# ADDINBRD2_V1.net
KiCad netlist of a schematic drawn in EAGLE
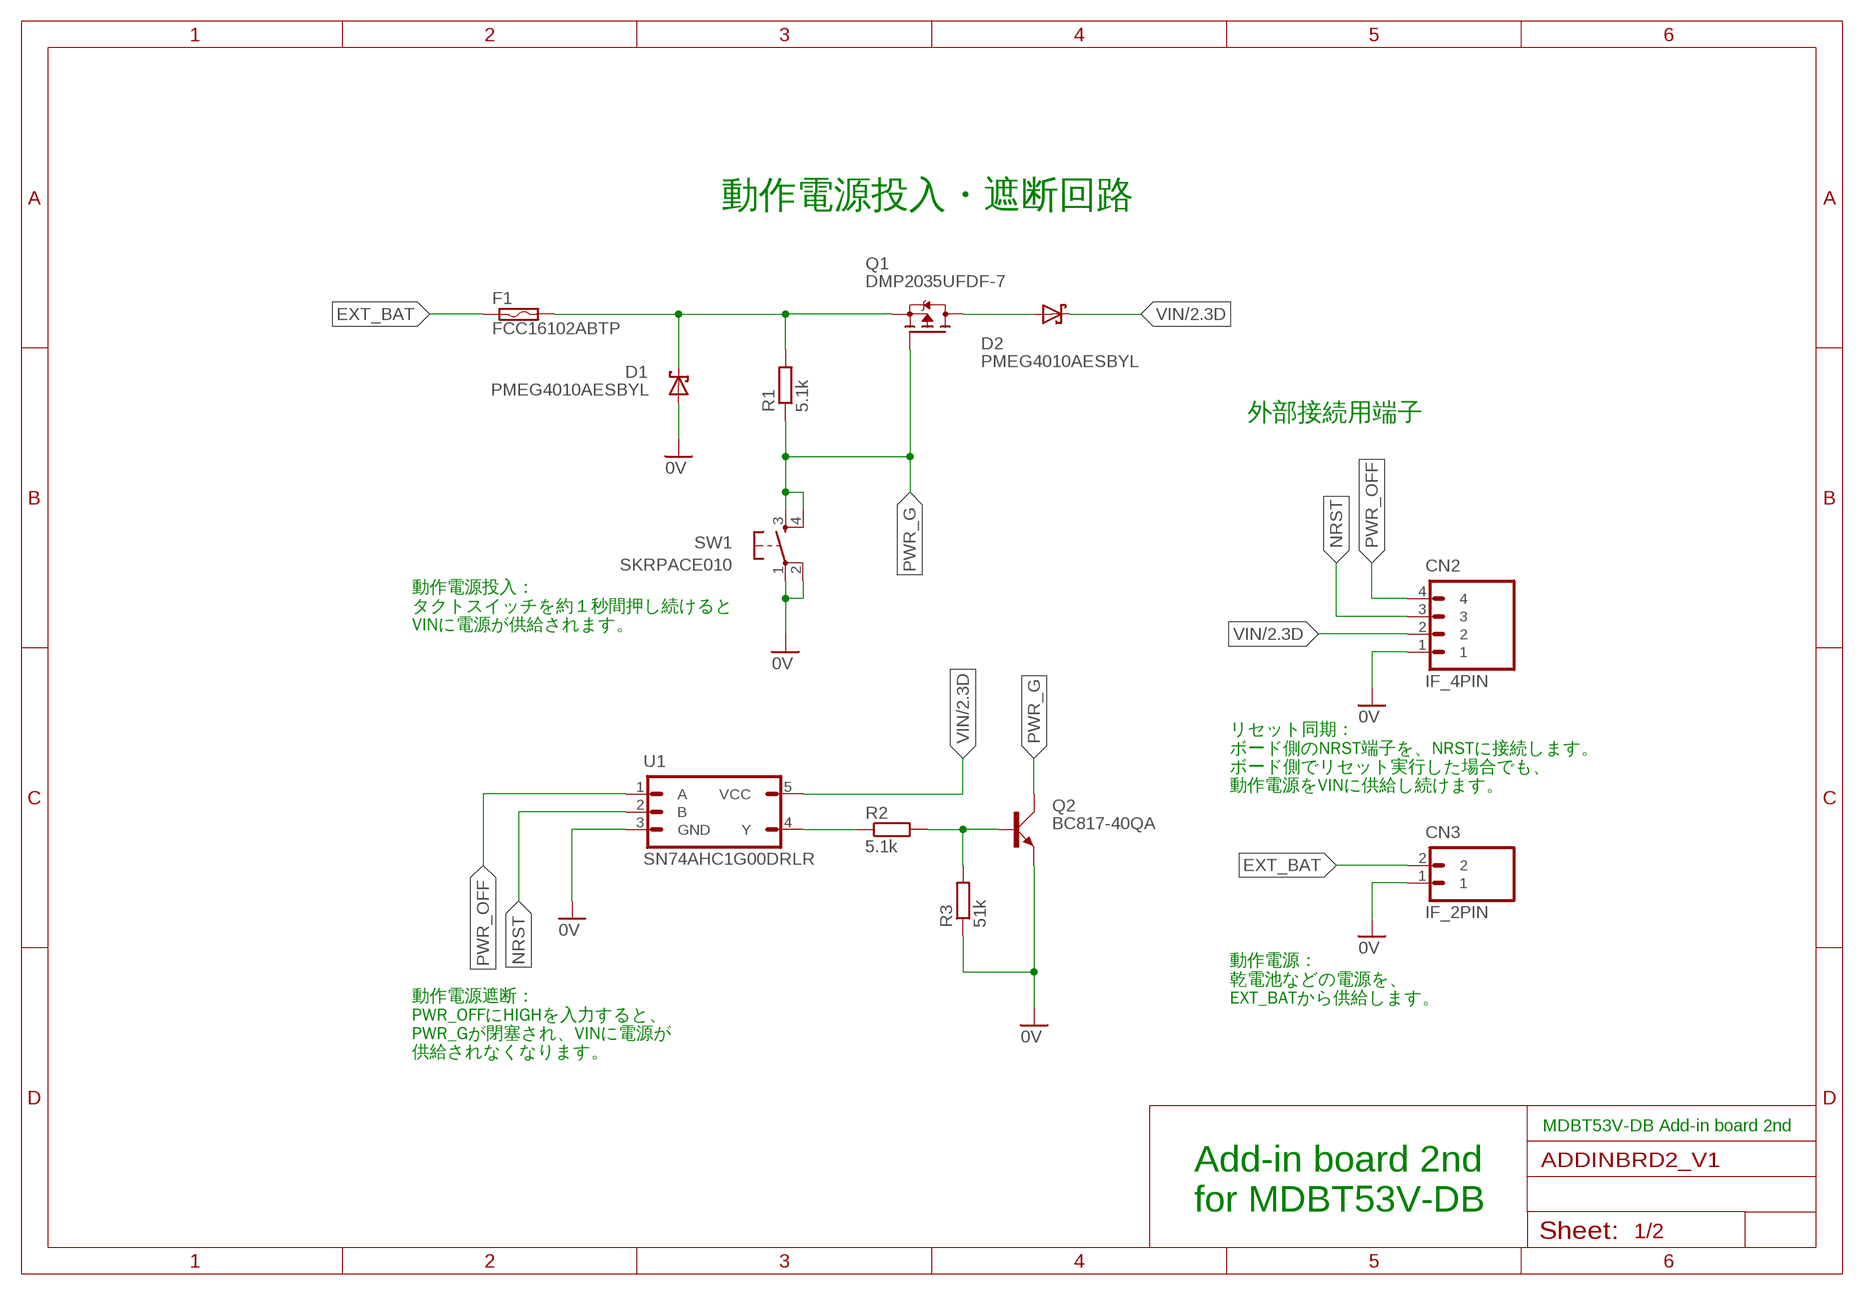
[diagram p0: schematic, sheet 1]
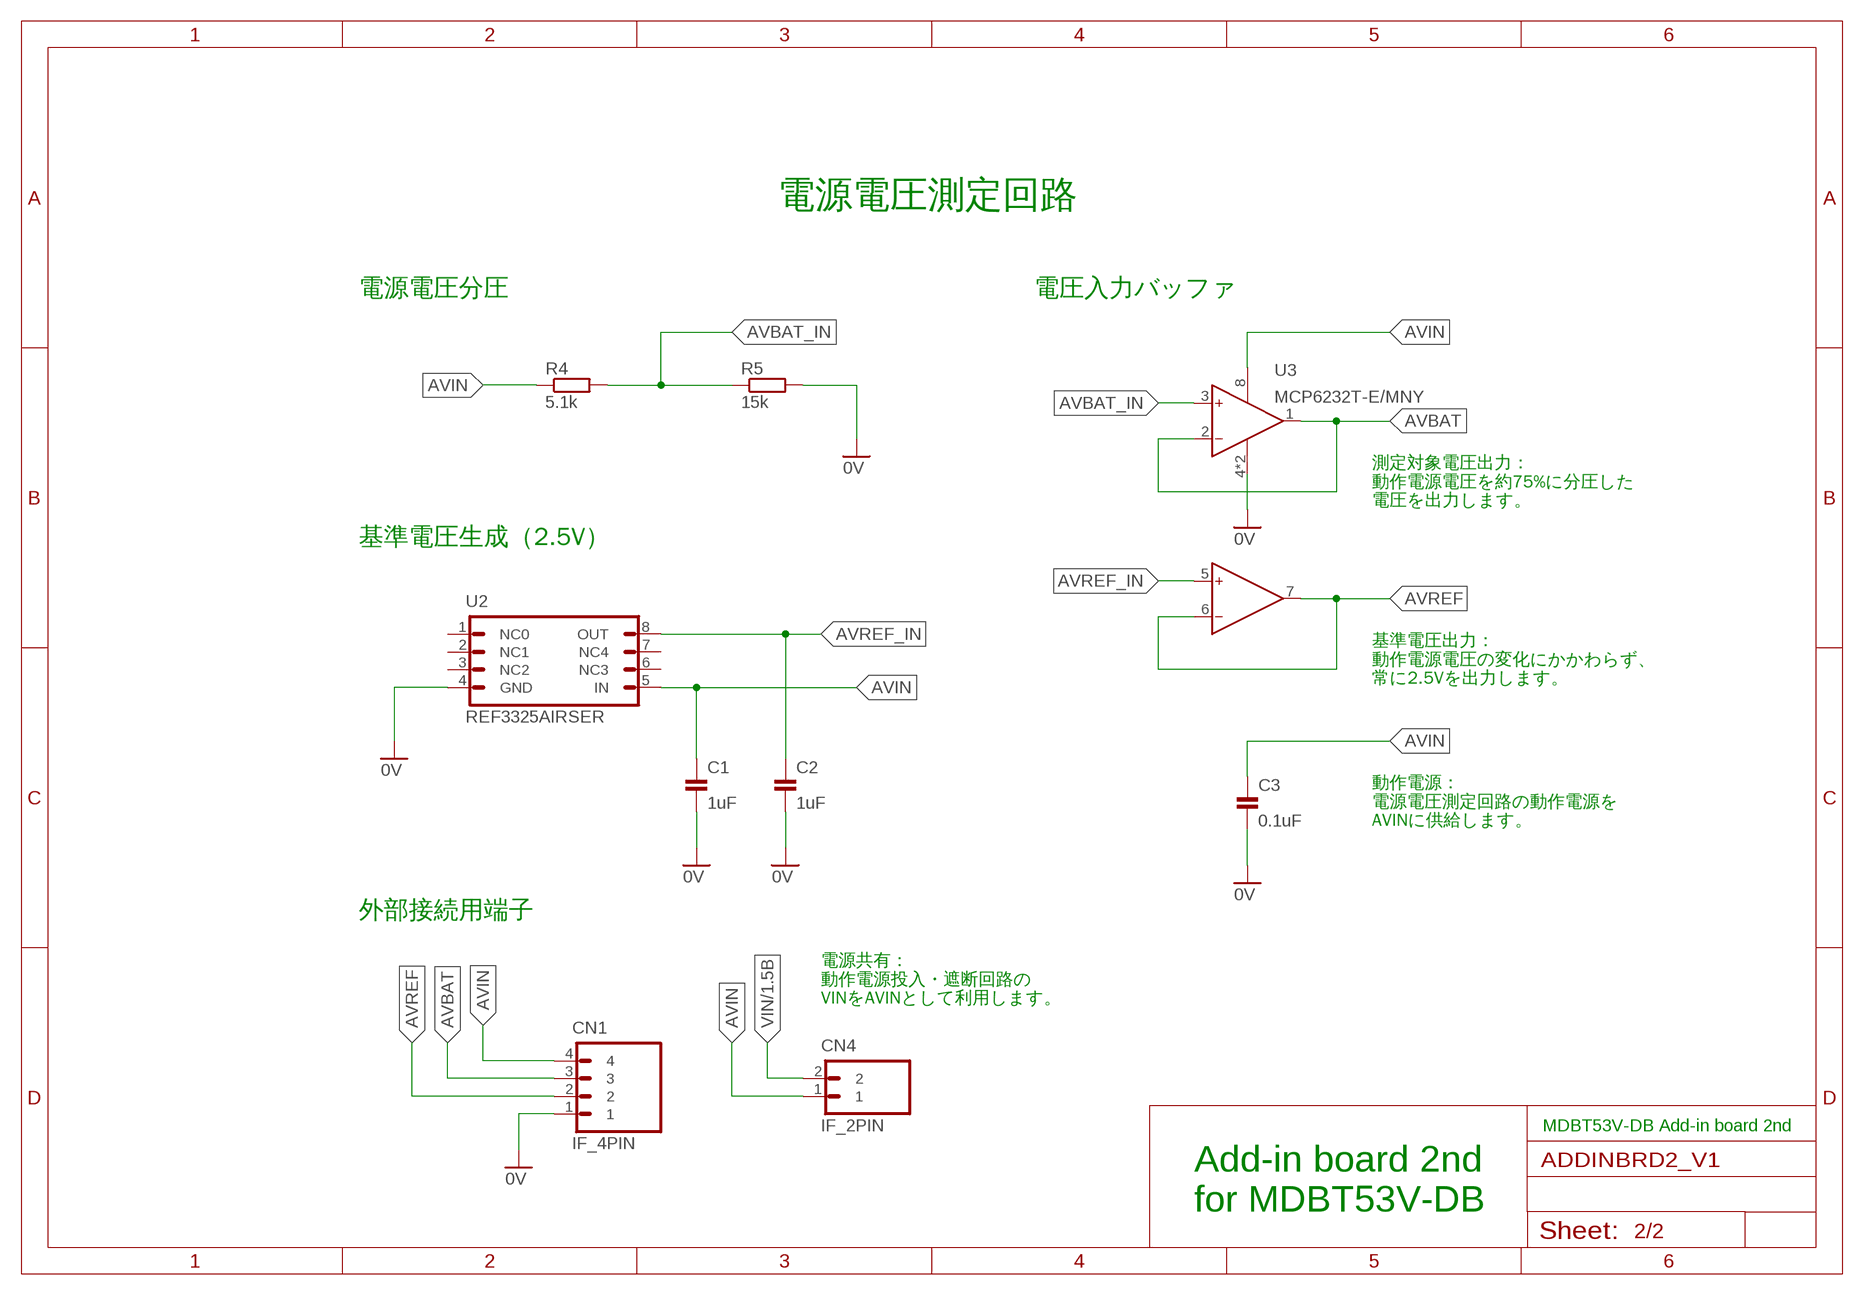
[diagram p1: schematic, sheet 2]

(export (version "E")
  (design (tool "Eeschema 10.0.6"))
  (components
    (comp (ref "CN2")
      (value "IF_4PIN")
      (footprint "eagle-import:HEADER_4PIN")
      (libsource (lib "eagle-import") (part "IF_4PIN"))
    )
    (comp (ref "CN3")
      (value "IF_2PIN")
      (footprint "eagle-import:HEADER_2PIN")
      (libsource (lib "eagle-import") (part "IF_2PIN"))
    )
    (comp (ref "D1")
      (value "PMEG4010AESBYL")
      (footprint "eagle-import:DSN1006-2")
      (libsource (lib "eagle-import") (part "PMEG4010AESBYL"))
    )
    (comp (ref "D2")
      (value "PMEG4010AESBYL")
      (footprint "eagle-import:DSN1006-2")
      (libsource (lib "eagle-import") (part "PMEG4010AESBYL"))
    )
    (comp (ref "F1")
      (value "FCC16102ABTP")
      (footprint "eagle-import:FCC16")
      (libsource (lib "eagle-import") (part "FCC16102ABTP"))
    )
    (comp (ref "Q1")
      (value "DMP2035UFDF-7")
      (footprint "eagle-import:U-DFN2020-6")
      (libsource (lib "eagle-import") (part "DMP2035UFDF-7"))
    )
    (comp (ref "Q2")
      (value "BC817-40QA")
      (footprint "eagle-import:DFN1010D-3")
      (libsource (lib "eagle-import") (part "BC817-40QA"))
    )
    (comp (ref "R1")
      (value "5.1k")
      (footprint "eagle-import:R0402N")
      (libsource (lib "eagle-import") (part "CRCW04025K10FKEDC"))
    )
    (comp (ref "R2")
      (value "5.1k")
      (footprint "eagle-import:R0402N")
      (libsource (lib "eagle-import") (part "CRCW04025K10FKEDC"))
    )
    (comp (ref "R3")
      (value "51k")
      (footprint "eagle-import:R0402N")
      (libsource (lib "eagle-import") (part "CRCW040251K0FKEDC"))
    )
    (comp (ref "SW1")
      (value "SKRPACE010")
      (footprint "eagle-import:SKRPACE010")
      (libsource (lib "eagle-import") (part "SKRPACE010"))
    )
    (comp (ref "U1")
      (value "SN74AHC1G00DRLR")
      (footprint "eagle-import:DRL0005A")
      (libsource (lib "eagle-import") (part "SN74AHC1G00DRLR"))
    )
    (comp (ref "C1")
      (value "1uF")
      (footprint "eagle-import:C0402")
      (libsource (lib "eagle-import") (part "TMK105AC6105KV-F"))
    )
    (comp (ref "C2")
      (value "1uF")
      (footprint "eagle-import:C0402")
      (libsource (lib "eagle-import") (part "TMK105AC6105KV-F"))
    )
    (comp (ref "C3")
      (value "0.1uF")
      (footprint "eagle-import:C0402")
      (libsource (lib "eagle-import") (part "UMK105B7104KV-FR"))
    )
    (comp (ref "CN1")
      (value "IF_4PIN")
      (footprint "eagle-import:HEADER_4PIN")
      (libsource (lib "eagle-import") (part "IF_4PIN"))
    )
    (comp (ref "CN4")
      (value "IF_2PIN")
      (footprint "eagle-import:HEADER_2PIN")
      (libsource (lib "eagle-import") (part "IF_2PIN"))
    )
    (comp (ref "R4")
      (value "5.1k")
      (footprint "eagle-import:R0402N")
      (libsource (lib "eagle-import") (part "ERA-2APB512X"))
    )
    (comp (ref "R5")
      (value "15k")
      (footprint "eagle-import:R0402N")
      (libsource (lib "eagle-import") (part "ERA-2APB153X"))
    )
    (comp (ref "U2")
      (value "REF3325AIRSER")
      (footprint "eagle-import:RSE0008A")
      (libsource (lib "eagle-import") (part "REF3325AIRSER"))
    )
    (comp (ref "U3")
      (value "MCP6232T-E/MNY")
      (footprint "eagle-import:TDFN-2X3")
      (libsource (lib "eagle-import") (part "MCP6232T-E/MNY"))
    )
  )
  (nets
    (net (code "1") (name "0V") (class "Default")
      (node (ref "C1") (pin "2") (pinfunction "2_2") (pintype "passive"))
      (node (ref "C2") (pin "2") (pinfunction "2_2") (pintype "passive"))
      (node (ref "C3") (pin "2") (pinfunction "2_2") (pintype "passive"))
      (node (ref "CN1") (pin "1") (pinfunction "1_1") (pintype "passive"))
      (node (ref "CN2") (pin "1") (pinfunction "1_1") (pintype "passive"))
      (node (ref "CN3") (pin "1") (pinfunction "1_1") (pintype "passive"))
      (node (ref "D1") (pin "1") (pinfunction "A_1") (pintype "passive"))
      (node (ref "Q2") (pin "2") (pinfunction "E_2") (pintype "passive"))
      (node (ref "R3") (pin "1") (pinfunction "1_1") (pintype "passive"))
      (node (ref "R5") (pin "2") (pinfunction "2_2") (pintype "passive"))
      (node (ref "SW1") (pin "1") (pinfunction "P_1") (pintype "passive"))
      (node (ref "SW1") (pin "2") (pinfunction "P1_2") (pintype "passive"))
      (node (ref "U1") (pin "3") (pinfunction "GND_3") (pintype "passive"))
      (node (ref "U2") (pin "4") (pinfunction "GND_4") (pintype "passive"))
      (node (ref "U3") (pin "4") (pinfunction "VSS_4") (pintype "passive"))
      (node (ref "U3") (pin "9") (pinfunction "VSS_9") (pintype "passive"))
    )
    (net (code "2") (name "AVBAT") (class "Default")
      (node (ref "CN1") (pin "3") (pinfunction "3_3") (pintype "passive"))
      (node (ref "U3") (pin "1") (pinfunction "VOUTA_1") (pintype "passive"))
      (node (ref "U3") (pin "2") (pinfunction "VINA-_2") (pintype "passive"))
    )
    (net (code "3") (name "AVBAT_IN") (class "Default")
      (node (ref "R4") (pin "2") (pinfunction "2_2") (pintype "passive"))
      (node (ref "R5") (pin "1") (pinfunction "1_1") (pintype "passive"))
      (node (ref "U3") (pin "3") (pinfunction "VINA+_3") (pintype "passive"))
    )
    (net (code "4") (name "AVIN") (class "Default")
      (node (ref "C1") (pin "1") (pinfunction "1_1") (pintype "passive"))
      (node (ref "C3") (pin "1") (pinfunction "1_1") (pintype "passive"))
      (node (ref "CN1") (pin "4") (pinfunction "4_4") (pintype "passive"))
      (node (ref "CN4") (pin "1") (pinfunction "1_1") (pintype "passive"))
      (node (ref "R4") (pin "1") (pinfunction "1_1") (pintype "passive"))
      (node (ref "U2") (pin "5") (pinfunction "IN_5") (pintype "passive"))
      (node (ref "U3") (pin "8") (pinfunction "VDD_8") (pintype "passive"))
    )
    (net (code "5") (name "AVREF") (class "Default")
      (node (ref "CN1") (pin "2") (pinfunction "2_2") (pintype "passive"))
      (node (ref "U3") (pin "6") (pinfunction "VINB-_6") (pintype "passive"))
      (node (ref "U3") (pin "7") (pinfunction "VOUTB_7") (pintype "passive"))
    )
    (net (code "6") (name "AVREF_IN") (class "Default")
      (node (ref "C2") (pin "1") (pinfunction "1_1") (pintype "passive"))
      (node (ref "U2") (pin "8") (pinfunction "OUT_8") (pintype "passive"))
      (node (ref "U3") (pin "5") (pinfunction "VINB+_5") (pintype "passive"))
    )
    (net (code "7") (name "EXT_BAT") (class "Default")
      (node (ref "CN3") (pin "2") (pinfunction "2_2") (pintype "passive"))
      (node (ref "F1") (pin "1") (pinfunction "1_1") (pintype "passive"))
    )
    (net (code "8") (name "NRST") (class "Default")
      (node (ref "CN2") (pin "3") (pinfunction "3_3") (pintype "passive"))
      (node (ref "U1") (pin "2") (pinfunction "B_2") (pintype "input"))
    )
    (net (code "9") (name "Net-(D1-C)") (class "Default")
      (node (ref "D1") (pin "2") (pinfunction "C_2") (pintype "passive"))
      (node (ref "F1") (pin "2") (pinfunction "2_2") (pintype "passive"))
      (node (ref "Q1") (pin "4") (pinfunction "S_4") (pintype "passive"))
      (node (ref "Q1") (pin "EXP2") (pinfunction "S_EXP2") (pintype "passive"))
      (node (ref "R1") (pin "2") (pinfunction "2_2") (pintype "passive"))
    )
    (net (code "10") (name "Net-(D2-A)") (class "Default")
      (node (ref "D2") (pin "1") (pinfunction "A_1") (pintype "passive"))
      (node (ref "Q1") (pin "1") (pinfunction "D_1") (pintype "passive"))
      (node (ref "Q1") (pin "2") (pinfunction "D_2") (pintype "passive"))
      (node (ref "Q1") (pin "5") (pinfunction "D_5") (pintype "passive"))
      (node (ref "Q1") (pin "6") (pinfunction "D_6") (pintype "passive"))
      (node (ref "Q1") (pin "EXP") (pinfunction "D_EXP") (pintype "passive"))
    )
    (net (code "11") (name "Net-(Q2-B)") (class "Default")
      (node (ref "Q2") (pin "1") (pinfunction "B_1") (pintype "passive"))
      (node (ref "R2") (pin "2") (pinfunction "2_2") (pintype "passive"))
      (node (ref "R3") (pin "2") (pinfunction "2_2") (pintype "passive"))
    )
    (net (code "12") (name "Net-(U1-Y)") (class "Default")
      (node (ref "R2") (pin "1") (pinfunction "1_1") (pintype "passive"))
      (node (ref "U1") (pin "4") (pinfunction "Y_4") (pintype "output"))
    )
    (net (code "13") (name "PWR_G") (class "Default")
      (node (ref "Q1") (pin "3") (pinfunction "G_3") (pintype "passive"))
      (node (ref "Q2") (pin "3") (pinfunction "C_3") (pintype "passive"))
      (node (ref "R1") (pin "1") (pinfunction "1_1") (pintype "passive"))
      (node (ref "SW1") (pin "3") (pinfunction "S_3") (pintype "passive"))
      (node (ref "SW1") (pin "4") (pinfunction "S1_4") (pintype "passive"))
    )
    (net (code "14") (name "PWR_OFF") (class "Default")
      (node (ref "CN2") (pin "4") (pinfunction "4_4") (pintype "passive"))
      (node (ref "U1") (pin "1") (pinfunction "A_1") (pintype "input"))
    )
    (net (code "15") (name "VIN") (class "Default")
      (node (ref "CN2") (pin "2") (pinfunction "2_2") (pintype "passive"))
      (node (ref "CN4") (pin "2") (pinfunction "2_2") (pintype "passive"))
      (node (ref "D2") (pin "2") (pinfunction "C_2") (pintype "passive"))
      (node (ref "U1") (pin "5") (pinfunction "VCC_5") (pintype "passive"))
    )
    (net (code "16") (name "unconnected-(U2-NC0-Pad1)") (class "Default")
      (node (ref "U2") (pin "1") (pinfunction "NC0_1") (pintype "passive"))
    )
    (net (code "17") (name "unconnected-(U2-NC1-Pad2)") (class "Default")
      (node (ref "U2") (pin "2") (pinfunction "NC1_2") (pintype "passive"))
    )
    (net (code "18") (name "unconnected-(U2-NC2-Pad3)") (class "Default")
      (node (ref "U2") (pin "3") (pinfunction "NC2_3") (pintype "passive"))
    )
    (net (code "19") (name "unconnected-(U2-NC3-Pad6)") (class "Default")
      (node (ref "U2") (pin "6") (pinfunction "NC3_6") (pintype "passive"))
    )
    (net (code "20") (name "unconnected-(U2-NC4-Pad7)") (class "Default")
      (node (ref "U2") (pin "7") (pinfunction "NC4_7") (pintype "passive"))
    )
  )
)
